# sharp_memory_breakout.net
KiCad netlist of a schematic drawn in EAGLE
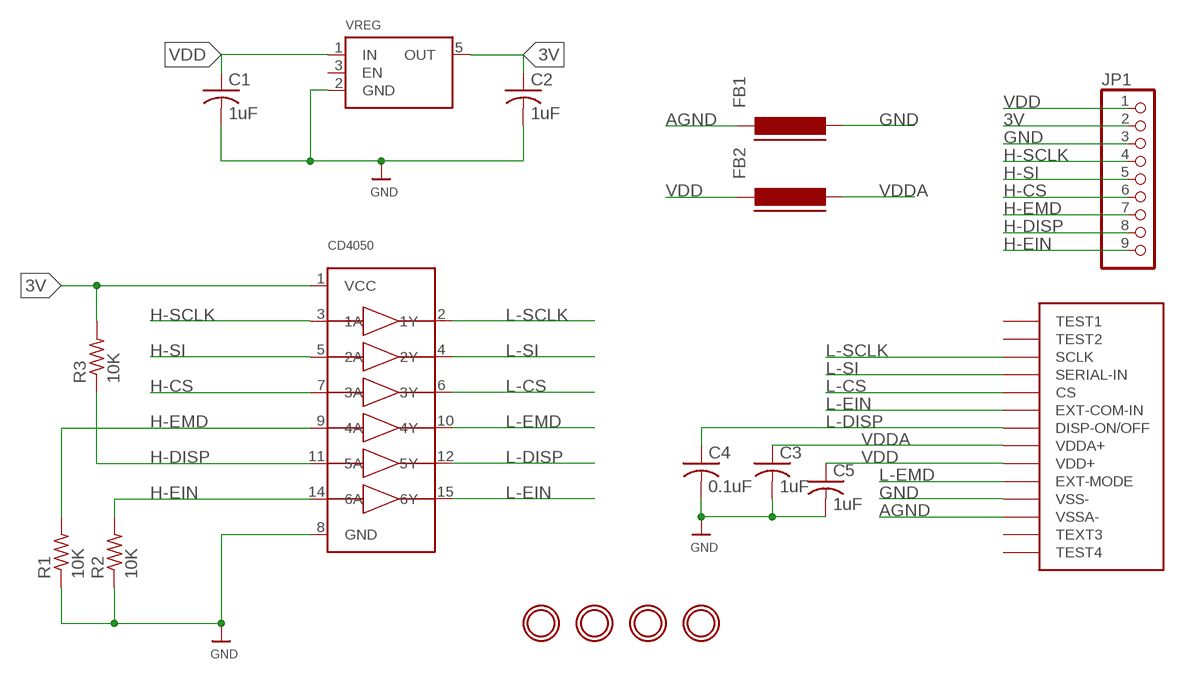
[diagram p0: schematic, sheet 1]

(export (version "E")
  (design (tool "Eeschema 10.0.6"))
  (components
    (comp (ref "C1")
      (value "1uF")
      (footprint "eagle-import:C0805K")
      (libsource (lib "eagle-import") (part "C-USC0805K"))
    )
    (comp (ref "C2")
      (value "1uF")
      (footprint "eagle-import:C0805K")
      (libsource (lib "eagle-import") (part "C-USC0805K"))
    )
    (comp (ref "C3")
      (value "1uF")
      (footprint "eagle-import:C0805K")
      (libsource (lib "eagle-import") (part "C-USC0805K"))
    )
    (comp (ref "C4")
      (value "0.1uF")
      (footprint "eagle-import:C0805K")
      (libsource (lib "eagle-import") (part "C-USC0805K"))
    )
    (comp (ref "C5")
      (value "1uF")
      (footprint "eagle-import:C0805K")
      (libsource (lib "eagle-import") (part "C-USC0805K"))
    )
    (comp (ref "CD4050")
      (value "74HC4050D")
      (footprint "eagle-import:SOIC16")
      (libsource (lib "eagle-import") (part "74HC4050D"))
    )
    (comp (ref "FB1")
      (value "FERRITE-0603")
      (footprint "eagle-import:FB603")
      (libsource (lib "eagle-import") (part "FERRITE-0603"))
    )
    (comp (ref "FB2")
      (value "FERRITE-0603")
      (footprint "eagle-import:FB603")
      (libsource (lib "eagle-import") (part "FERRITE-0603"))
    )
    (comp (ref "JP1")
      (value "PINHD-1X9")
      (footprint "eagle-import:1X09-BIG")
      (libsource (lib "eagle-import") (part "PINHD-1X9"))
    )
    (comp (ref "R1")
      (value "10K")
      (footprint "eagle-import:R0805")
      (libsource (lib "eagle-import") (part "R-US_R0805"))
    )
    (comp (ref "R2")
      (value "10K")
      (footprint "eagle-import:R0805")
      (libsource (lib "eagle-import") (part "R-US_R0805"))
    )
    (comp (ref "R3")
      (value "10K")
      (footprint "eagle-import:R0805")
      (libsource (lib "eagle-import") (part "R-US_R0805"))
    )
    (comp (ref "U$1")
      (value "SHARP-MEMORY")
      (footprint "eagle-import:SHARP-MEMORY")
      (libsource (lib "eagle-import") (part "SHARP-MEMORY"))
    )
    (comp (ref "U$2")
      (value "MOUNTINGHOLE3.0THIN")
      (footprint "eagle-import:MOUNTINGHOLE_3.0_PLATEDTHIN")
      (libsource (lib "eagle-import") (part "MOUNTINGHOLE3.0THIN"))
    )
    (comp (ref "U$3")
      (value "MOUNTINGHOLE3.0THIN")
      (footprint "eagle-import:MOUNTINGHOLE_3.0_PLATEDTHIN")
      (libsource (lib "eagle-import") (part "MOUNTINGHOLE3.0THIN"))
    )
    (comp (ref "U$4")
      (value "MOUNTINGHOLE3.0THIN")
      (footprint "eagle-import:MOUNTINGHOLE_3.0_PLATEDTHIN")
      (libsource (lib "eagle-import") (part "MOUNTINGHOLE3.0THIN"))
    )
    (comp (ref "U$5")
      (value "MOUNTINGHOLE3.0THIN")
      (footprint "eagle-import:MOUNTINGHOLE_3.0_PLATEDTHIN")
      (libsource (lib "eagle-import") (part "MOUNTINGHOLE3.0THIN"))
    )
    (comp (ref "VREG")
      (value "ADP121")
      (footprint "eagle-import:SOT23-5")
      (libsource (lib "eagle-import") (part "ADP121"))
    )
  )
  (nets
    (net (code "1") (name "/AGND") (class "Default")
      (node (ref "FB1") (pin "1") (pinfunction "1_1") (pintype "passive"))
      (node (ref "U$1") (pin "P$12") (pinfunction "VSSA-_P$12") (pintype "bidirectional"))
    )
    (net (code "2") (name "/H-CS") (class "Default")
      (node (ref "CD4050") (pin "7") (pinfunction "3A_7") (pintype "bidirectional"))
      (node (ref "JP1") (pin "6") (pinfunction "6_6") (pintype "passive"))
    )
    (net (code "3") (name "/H-DISP") (class "Default")
      (node (ref "CD4050") (pin "11") (pinfunction "5A_11") (pintype "bidirectional"))
      (node (ref "JP1") (pin "8") (pinfunction "8_8") (pintype "passive"))
      (node (ref "R3") (pin "1") (pinfunction "1_1") (pintype "passive"))
    )
    (net (code "4") (name "/H-EIN") (class "Default")
      (node (ref "CD4050") (pin "14") (pinfunction "6A_14") (pintype "bidirectional"))
      (node (ref "JP1") (pin "9") (pinfunction "9_9") (pintype "passive"))
      (node (ref "R2") (pin "2") (pinfunction "2_2") (pintype "passive"))
    )
    (net (code "5") (name "/H-EMD") (class "Default")
      (node (ref "CD4050") (pin "9") (pinfunction "4A_9") (pintype "bidirectional"))
      (node (ref "JP1") (pin "7") (pinfunction "7_7") (pintype "passive"))
      (node (ref "R1") (pin "2") (pinfunction "2_2") (pintype "passive"))
    )
    (net (code "6") (name "/H-SCLK") (class "Default")
      (node (ref "CD4050") (pin "3") (pinfunction "1A_3") (pintype "bidirectional"))
      (node (ref "JP1") (pin "4") (pinfunction "4_4") (pintype "passive"))
    )
    (net (code "7") (name "/H-SI") (class "Default")
      (node (ref "CD4050") (pin "5") (pinfunction "2A_5") (pintype "bidirectional"))
      (node (ref "JP1") (pin "5") (pinfunction "5_5") (pintype "passive"))
    )
    (net (code "8") (name "/L-CS") (class "Default")
      (node (ref "CD4050") (pin "6") (pinfunction "3Y_6") (pintype "bidirectional"))
      (node (ref "U$1") (pin "P$5") (pinfunction "CS_P$5") (pintype "bidirectional"))
    )
    (net (code "9") (name "/L-DISP") (class "Default")
      (node (ref "C4") (pin "1") (pinfunction "1_1") (pintype "passive"))
      (node (ref "CD4050") (pin "12") (pinfunction "5Y_12") (pintype "bidirectional"))
      (node (ref "U$1") (pin "P$7") (pinfunction "DISP-ON/OFF_P$7") (pintype "bidirectional"))
    )
    (net (code "10") (name "/L-EIN") (class "Default")
      (node (ref "CD4050") (pin "15") (pinfunction "6Y_15") (pintype "bidirectional"))
      (node (ref "U$1") (pin "P$6") (pinfunction "EXT-COM-IN_P$6") (pintype "bidirectional"))
    )
    (net (code "11") (name "/L-EMD") (class "Default")
      (node (ref "CD4050") (pin "10") (pinfunction "4Y_10") (pintype "bidirectional"))
      (node (ref "U$1") (pin "P$10") (pinfunction "EXT-MODE_P$10") (pintype "bidirectional"))
    )
    (net (code "12") (name "/L-SCLK") (class "Default")
      (node (ref "CD4050") (pin "2") (pinfunction "1Y_2") (pintype "bidirectional"))
      (node (ref "U$1") (pin "P$3") (pinfunction "SCLK_P$3") (pintype "bidirectional"))
    )
    (net (code "13") (name "/L-SI") (class "Default")
      (node (ref "CD4050") (pin "4") (pinfunction "2Y_4") (pintype "bidirectional"))
      (node (ref "U$1") (pin "P$4") (pinfunction "SERIAL-IN_P$4") (pintype "bidirectional"))
    )
    (net (code "14") (name "/VDDA") (class "Default")
      (node (ref "C3") (pin "1") (pinfunction "1_1") (pintype "passive"))
      (node (ref "FB2") (pin "2") (pinfunction "2_2") (pintype "passive"))
      (node (ref "U$1") (pin "P$8") (pinfunction "VDDA+_P$8") (pintype "bidirectional"))
    )
    (net (code "15") (name "3V") (class "Default")
      (node (ref "C2") (pin "1") (pinfunction "1_1") (pintype "passive"))
      (node (ref "CD4050") (pin "1") (pinfunction "VCC_1") (pintype "bidirectional"))
      (node (ref "JP1") (pin "2") (pinfunction "2_2") (pintype "passive"))
      (node (ref "R3") (pin "2") (pinfunction "2_2") (pintype "passive"))
      (node (ref "VREG") (pin "5") (pinfunction "OUT_5") (pintype "bidirectional"))
    )
    (net (code "16") (name "GND") (class "Default")
      (node (ref "C1") (pin "2") (pinfunction "2_2") (pintype "passive"))
      (node (ref "C2") (pin "2") (pinfunction "2_2") (pintype "passive"))
      (node (ref "C3") (pin "2") (pinfunction "2_2") (pintype "passive"))
      (node (ref "C4") (pin "2") (pinfunction "2_2") (pintype "passive"))
      (node (ref "C5") (pin "2") (pinfunction "2_2") (pintype "passive"))
      (node (ref "CD4050") (pin "8") (pinfunction "GND_8") (pintype "bidirectional"))
      (node (ref "FB1") (pin "2") (pinfunction "2_2") (pintype "passive"))
      (node (ref "JP1") (pin "3") (pinfunction "3_3") (pintype "passive"))
      (node (ref "R1") (pin "1") (pinfunction "1_1") (pintype "passive"))
      (node (ref "R2") (pin "1") (pinfunction "1_1") (pintype "passive"))
      (node (ref "U$1") (pin "P$11") (pinfunction "VSS-_P$11") (pintype "bidirectional"))
      (node (ref "VREG") (pin "2") (pinfunction "GND_2") (pintype "bidirectional"))
    )
    (net (code "17") (name "VDD") (class "Default")
      (node (ref "C1") (pin "1") (pinfunction "1_1") (pintype "passive"))
      (node (ref "C5") (pin "1") (pinfunction "1_1") (pintype "passive"))
      (node (ref "FB2") (pin "1") (pinfunction "1_1") (pintype "passive"))
      (node (ref "JP1") (pin "1") (pinfunction "1_1") (pintype "passive"))
      (node (ref "U$1") (pin "P$9") (pinfunction "VDD+_P$9") (pintype "bidirectional"))
      (node (ref "VREG") (pin "1") (pinfunction "IN_1") (pintype "bidirectional"))
    )
    (net (code "18") (name "unconnected-(U$1-TEST1-PadP$1)") (class "Default")
      (node (ref "U$1") (pin "P$1") (pinfunction "TEST1_P$1") (pintype "bidirectional"))
    )
    (net (code "19") (name "unconnected-(U$1-TEST2-PadP$2)") (class "Default")
      (node (ref "U$1") (pin "P$2") (pinfunction "TEST2_P$2") (pintype "bidirectional"))
    )
    (net (code "20") (name "unconnected-(U$1-TEST4-PadP$14)") (class "Default")
      (node (ref "U$1") (pin "P$14") (pinfunction "TEST4_P$14") (pintype "bidirectional"))
    )
    (net (code "21") (name "unconnected-(U$1-TEXT3-PadP$13)") (class "Default")
      (node (ref "U$1") (pin "P$13") (pinfunction "TEXT3_P$13") (pintype "bidirectional"))
    )
    (net (code "22") (name "unconnected-(VREG-EN-Pad3)") (class "Default")
      (node (ref "VREG") (pin "3") (pinfunction "EN_3") (pintype "bidirectional"))
    )
  )
)
